# Peripheral.net
KiCad netlist of a schematic drawn in Altium Designer
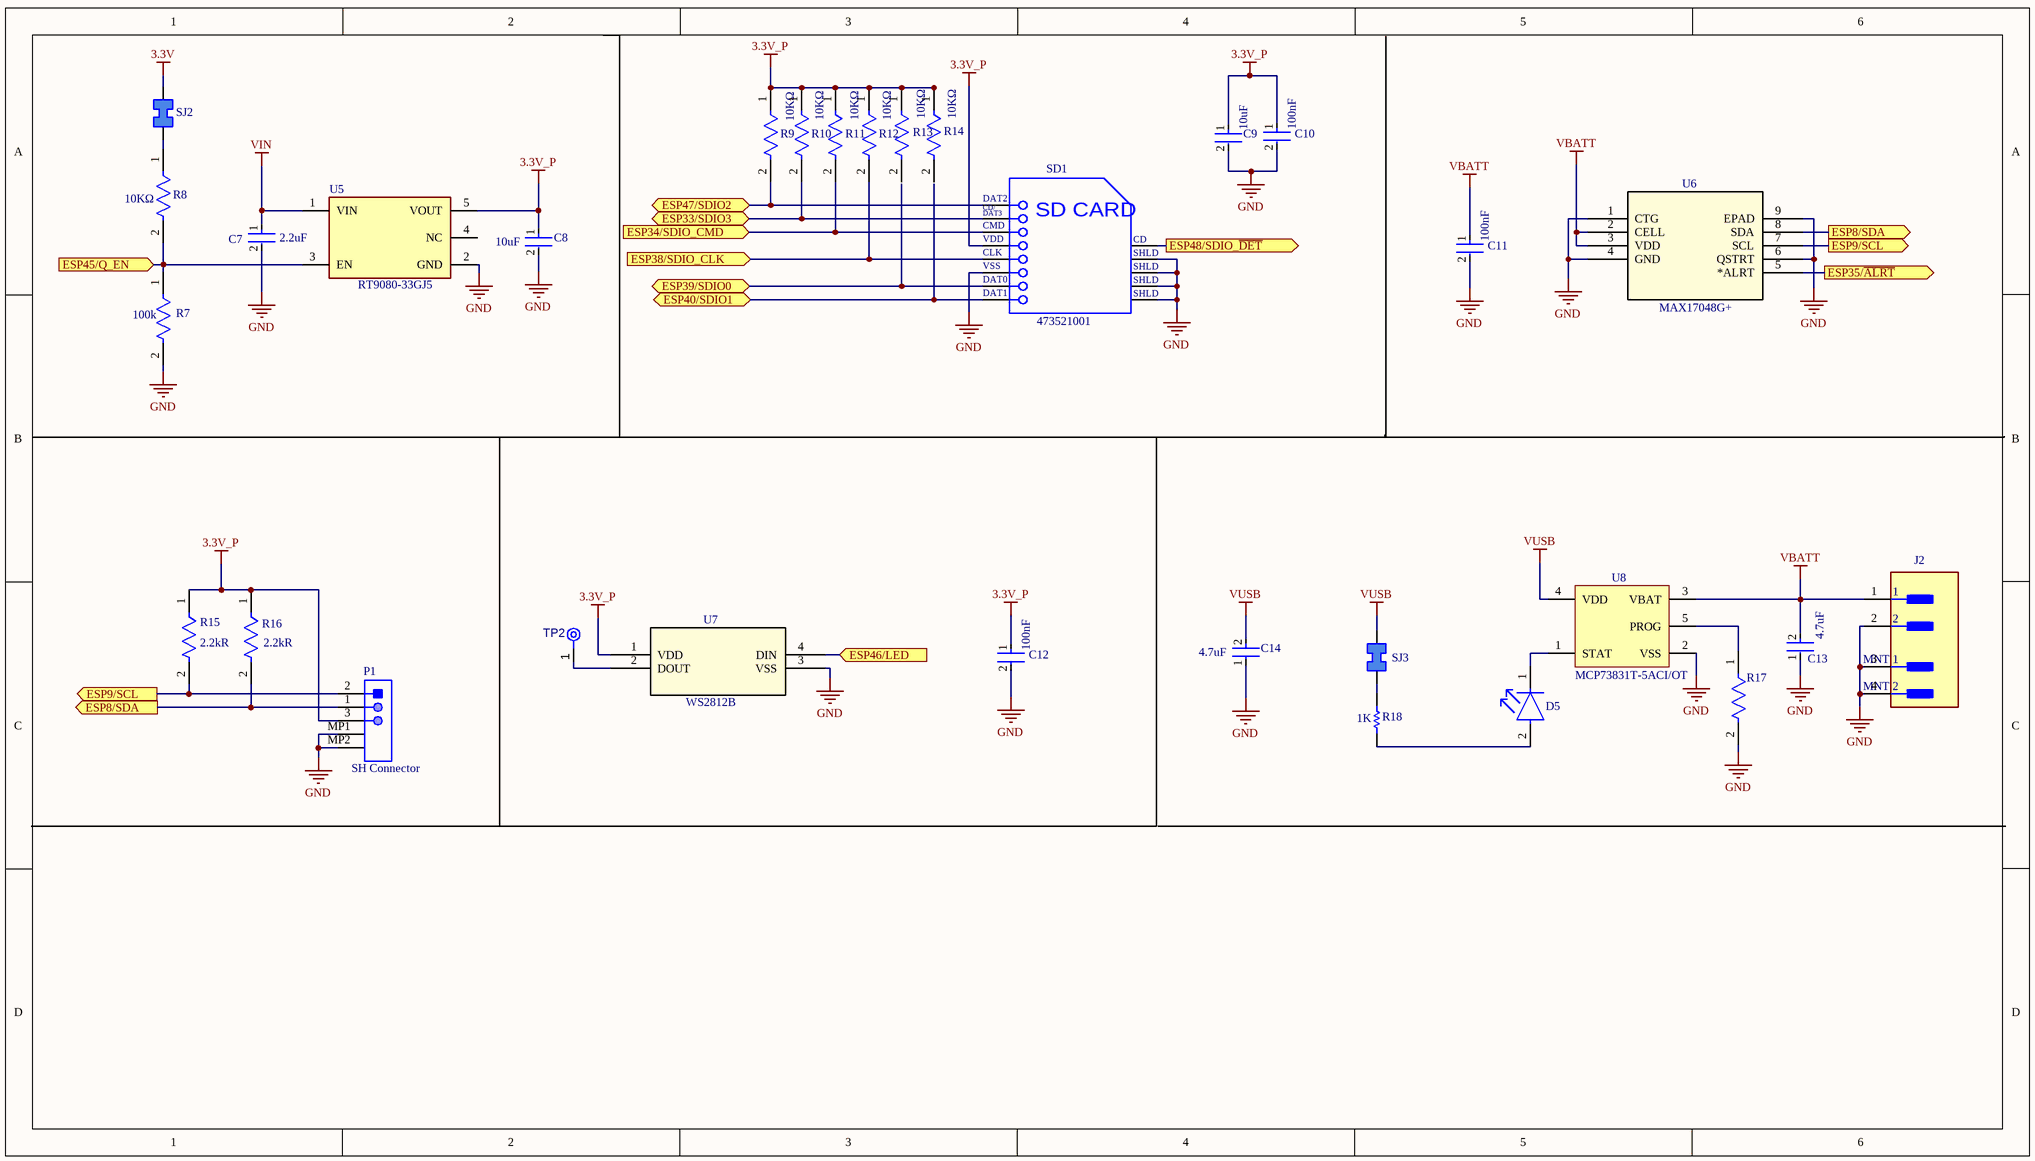
[diagram p0: Peripheral.SchDoc]

(export (version "E")
  (design (tool "Eeschema 10.0.6"))
  (components
    (comp (ref "C7")
      (value "GRM155C81A225KE44D")
      (footprint "FP-GRM155-0_1-IPC_C")
      (description "Chip Multilayer Ceramic Capacitors for General Purpose, 0402, 2.2uF, X6S, 22%, 10%, 10V")
      (fields (field (name "TOLERANCE") "10%") (field (name "CAPACITANCE") "2.2uF"))
      (libsource (lib "Altium Content Vault") (part "11868f565c42a9108669ba33697ecf6"))
    )
    (comp (ref "C8")
      (value "CL21A106MQFNNNE")
      (footprint "FP-CL21-IPC_C")
      (description "CL21 Series 0805 10uF 6.3V ±20% Tolerance X5R Multilayer Ceramic Chip Capacitor")
      (fields (field (name "CAPACITANCE") "10uF") (field (name "TOLERANCE") "20%"))
      (libsource (lib "Altium Content Vault") (part "b4654b650e69147ec39a6b967a45e02"))
    )
    (comp (ref "C9")
      (value "CL21A106MQFNNNE")
      (footprint "FP-CL21-IPC_C")
      (description "CL21 Series 0805 10uF 6.3V ±20% Tolerance X5R Multilayer Ceramic Chip Capacitor")
      (fields (field (name "CAPACITANCE") "10uF") (field (name "TOLERANCE") "20%"))
      (libsource (lib "Altium Content Vault") (part "b4654b650e69147ec39a6b967a45e02"))
    )
    (comp (ref "C10")
      (value "GRM033C70J104KE14D")
      (footprint "FP-GRM033-0_03-IPC_B")
      (description "Chip Multilayer Ceramic Capacitors for General Purpose, 0201, 0.10uF, X7S, 22%, 10%, 6.3V")
      (fields (field (name "CAPACITANCE") "100nF") (field (name "TOLERANCE") "10%"))
      (libsource (lib "Altium Content Vault") (part "b4654b650e69147ec39a6b967a45e02"))
    )
    (comp (ref "C11")
      (value "GRM033C70J104KE14D")
      (footprint "FP-GRM033-0_03-IPC_B")
      (description "Chip Multilayer Ceramic Capacitors for General Purpose, 0201, 0.10uF, X7S, 22%, 10%, 6.3V")
      (fields (field (name "CAPACITANCE") "100nF") (field (name "TOLERANCE") "10%"))
      (libsource (lib "Altium Content Vault") (part "b4654b650e69147ec39a6b967a45e02"))
    )
    (comp (ref "C12")
      (value "GRM033C70J104KE14D")
      (footprint "FP-GRM033-0_03-IPC_B")
      (description "Chip Multilayer Ceramic Capacitors for General Purpose, 0201, 0.10uF, X7S, 22%, 10%, 6.3V")
      (fields (field (name "CAPACITANCE") "100nF") (field (name "TOLERANCE") "10%"))
      (libsource (lib "Altium Content Vault") (part "b4654b650e69147ec39a6b967a45e02"))
    )
    (comp (ref "C13")
      (value "JMK105BC6475MV-F")
      (footprint "FP-0402-L_1_0_0_15-W_0_5-IPC_C")
      (description "None")
      (fields (field (name "CAPACITANCE") "4.7uF") (field (name "TOLERANCE") "20%"))
      (libsource (lib "Altium Content Vault") (part "236180d848d6139a670b325ea6854c9"))
    )
    (comp (ref "C14")
      (value "GRM219R6YA475MA73D")
      (footprint "FP-GRM219-0_15-0_1-IPC_C")
      (description "Chip Multilayer Ceramic Capacitors for General Purpose, 0805, 4.7uF, X5R, 15%, 20%, 35V")
      (fields
        (field (name "CAPACITANCE") "4.7uF")
        (field (name "VOLTAGE") "35V")
        (field (name "TOLERANCE") "20%")
      )
      (libsource (lib "Altium Content Vault") (part "236180d848d6139a670b325ea6854c9"))
    )
    (comp (ref "D5")
      (value "LTST-C191KSKT")
      (footprint "FP-LTST-C191KSKT-MFG")
      (description "LED YELLOW CLEAR SMD")
      (libsource (lib "Altium Content Vault") (part "8706943c75ba83719d021d2fdc84c58"))
    )
    (comp (ref "J2")
      (value "SM02B-SRSS-TB (LF)(SN)")
      (footprint "FP-SM02B-SRSS-TB_LF_SN-MFG")
      (description "CONN HEADER SMD R/A 2POS 1MM")
      (libsource (lib "Altium Content Vault") (part "029478cb6d4f2fad0cd2a245525ee6d"))
    )
    (comp (ref "P1")
      (value "SH Connector")
      (footprint "JST-SM03B-SRSS-TB_V")
      (description "Male Header, Pitch 1 mm, 1 x 3 Position, Height 2.9 mm, -25 to 85 degC, RoHS, Tape and Reel")
      (fields (field (name "MANUFACTURER") "JST"))
      (libsource (lib "Altium Content Vault") (part "CN-1P-2M-R3"))
    )
    (comp (ref "R7")
      (value "CRCW0402100KFKEDC")
      (footprint "FP-CRCW0402-C-e3-MFG")
      (description "RES 100K OHM 1% 1/16W 0402")
      (fields (field (name "TOLERANCE") "1%") (field (name "RESISTANCE") "100k"))
      (libsource (lib "Altium Content Vault") (part "1029c3af85768c4190bb7ad29bc67b5"))
    )
    (comp (ref "R8")
      (value "10KΩ")
      (footprint "FP-RT0201-MFG")
      (description "RES SMD 10K OHM 1% 1/20W 0201")
      (fields
        (field (name "MANUFACTURER PART NUMBER") "RT0201FRE0710KL")
        (field (name "MANUFACTURER") "Yageo")
      )
      (libsource (lib "Altium Content Vault") (part "1029c3af85768c4190bb7ad29bc67b5"))
    )
    (comp (ref "R9")
      (value "10KΩ")
      (footprint "FP-RT0201-MFG")
      (description "RES SMD 10K OHM 1% 1/20W 0201")
      (fields
        (field (name "MANUFACTURER PART NUMBER") "RT0201FRE0710KL")
        (field (name "MANUFACTURER") "Yageo")
      )
      (libsource (lib "Altium Content Vault") (part "1029c3af85768c4190bb7ad29bc67b5"))
    )
    (comp (ref "R10")
      (value "10KΩ")
      (footprint "FP-RT0201-MFG")
      (description "RES SMD 10K OHM 1% 1/20W 0201")
      (fields
        (field (name "MANUFACTURER PART NUMBER") "RT0201FRE0710KL")
        (field (name "MANUFACTURER") "Yageo")
      )
      (libsource (lib "Altium Content Vault") (part "1029c3af85768c4190bb7ad29bc67b5"))
    )
    (comp (ref "R11")
      (value "10KΩ")
      (footprint "FP-RT0201-MFG")
      (description "RES SMD 10K OHM 1% 1/20W 0201")
      (fields
        (field (name "MANUFACTURER PART NUMBER") "RT0201FRE0710KL")
        (field (name "MANUFACTURER") "Yageo")
      )
      (libsource (lib "Altium Content Vault") (part "1029c3af85768c4190bb7ad29bc67b5"))
    )
    (comp (ref "R12")
      (value "10KΩ")
      (footprint "FP-RT0201-MFG")
      (description "RES SMD 10K OHM 1% 1/20W 0201")
      (fields
        (field (name "MANUFACTURER PART NUMBER") "RT0201FRE0710KL")
        (field (name "MANUFACTURER") "Yageo")
      )
      (libsource (lib "Altium Content Vault") (part "1029c3af85768c4190bb7ad29bc67b5"))
    )
    (comp (ref "R13")
      (value "10KΩ")
      (footprint "FP-RT0201-MFG")
      (description "RES SMD 10K OHM 1% 1/20W 0201")
      (fields
        (field (name "MANUFACTURER PART NUMBER") "RT0201FRE0710KL")
        (field (name "MANUFACTURER") "Yageo")
      )
      (libsource (lib "Altium Content Vault") (part "1029c3af85768c4190bb7ad29bc67b5"))
    )
    (comp (ref "R14")
      (value "10KΩ")
      (footprint "FP-RT0201-MFG")
      (description "RES SMD 10K OHM 1% 1/20W 0201")
      (fields
        (field (name "MANUFACTURER PART NUMBER") "RT0201FRE0710KL")
        (field (name "MANUFACTURER") "Yageo")
      )
      (libsource (lib "Altium Content Vault") (part "1029c3af85768c4190bb7ad29bc67b5"))
    )
    (comp (ref "R15")
      (value "CRCW04022K20FKEDC")
      (footprint "FP-CRCW0402-e3-IPC_B")
      (description "RES 2.2K OHM 1% 1/16W 0402")
      (fields (field (name "TOLERANCE") "1%") (field (name "RESISTANCE") "2.2kR"))
      (libsource (lib "Altium Content Vault") (part "1029c3af85768c4190bb7ad29bc67b5"))
    )
    (comp (ref "R16")
      (value "CRCW04022K20FKEDC")
      (footprint "FP-CRCW0402-e3-IPC_B")
      (description "RES 2.2K OHM 1% 1/16W 0402")
      (fields (field (name "TOLERANCE") "1%") (field (name "RESISTANCE") "2.2kR"))
      (libsource (lib "Altium Content Vault") (part "1029c3af85768c4190bb7ad29bc67b5"))
    )
    (comp (ref "R17")
      (value "CR0402AFX-2001GLF")
      (footprint "FP-CR0402A-IPC_A")
      (description "AEC-Q200 Compliant Chip Resistors 0402 2kΩ 0.063W 1% 100ppm/°C")
      (libsource (lib "Altium Content Vault") (part "1029c3af85768c4190bb7ad29bc67b5"))
    )
    (comp (ref "R18")
      (value "1-1622826-8")
      (footprint "RESC1005X40X25ML10T10")
      (fields (field (name "MANUFACTURER") "TE Connectivity / AMP") (field (name "RESISTANCE") "1K"))
      (libsource (lib "Altium Content Vault") (part "RES"))
    )
    (comp (ref "SD1")
      (value "473521001")
      (footprint "MOLX-473521001_V")
      (description "MicroSD(TM), Pitch 1.1 mm, 8 Position, Height 1.88 mm, -20 to 85 degC, RoHS, Tape and Reel")
      (fields (field (name "MANUFACTURER") "Molex"))
      (libsource (lib "Altium Content Vault") (part "CN-SD-8-1SW-4S"))
    )
    (comp (ref "SJ2")
      (value "Solder Jumper")
      (footprint "Solder Jumper-Footprint-1")
      (description "2 pad Solder Jumper")
      (libsource (lib "Shuvendu Das") (part "Solder Jumper"))
    )
    (comp (ref "SJ3")
      (value "Solder Jumper")
      (footprint "Solder Jumper-Footprint-1")
      (description "2 pad Solder Jumper")
      (libsource (lib "Shuvendu Das") (part "Solder Jumper"))
    )
    (comp (ref "TP2")
      (value "TPAD6R")
      (footprint "TP06R")
      (description "0.6mm round")
      (libsource (lib "Shuvendu Das") (part "CMP-001-0001-4"))
    )
    (comp (ref "U5")
      (value "RT9080-33GJ5")
      (footprint "FP-RT9080-33GJ5-IPC_C")
      (description "IC REG LIN 3.3V 600MA TSOT23-5")
      (libsource (lib "Altium Content Vault") (part "f644620f29190e8f0733f9129712cb2"))
    )
    (comp (ref "U6")
      (value "MAX17048G+")
      (footprint "21-0168_T822+3_MXM")
      (description "3ÂµA 1-Cell/2-Cell Fuel Gauge with ModelGauge")
      (fields (field (name "COPYRIGHT") "Copyright (C) 2025 Ultra Librarian. All rights reserved."))
      (libsource (lib "MAX17048G&plus_") (part "MAX17048G+"))
    )
    (comp (ref "U7")
      (value "WS2812B")
      (footprint "WS2812B:WS2812B_WDS")
      (description "No Description Available")
      (fields (field (name "COPYRIGHT") "Copyright (C) 2025 Ultra Librarian. All rights reserved."))
      (libsource (lib "WS2812B") (part "WS2812B"))
    )
    (comp (ref "U8")
      (value "MCP73831T-5ACI/OT")
      (footprint "SOT-23-OT5_N")
      (libsource (lib "Altium Content Vault") (part "PM-BM-MCP73831-SOT5"))
    )
  )
  (nets
    (net (code "1") (name "/ESP8{slash}SDA") (class "Default")
      (node (ref "P1") (pin "1") (pinfunction "1_1") (pintype "passive"))
      (node (ref "R16") (pin "2") (pinfunction "2_2") (pintype "passive"))
      (node (ref "U6") (pin "8") (pinfunction "SDA_8") (pintype "passive"))
    )
    (net (code "2") (name "/ESP9{slash}SCL") (class "Default")
      (node (ref "P1") (pin "2") (pinfunction "2_2") (pintype "passive"))
      (node (ref "R15") (pin "2") (pinfunction "2_2") (pintype "passive"))
      (node (ref "U6") (pin "7") (pinfunction "SCL_7") (pintype "passive"))
    )
    (net (code "3") (name "/ESP33{slash}SDIO3") (class "Default")
      (node (ref "R10") (pin "2") (pinfunction "2_2") (pintype "passive"))
      (node (ref "SD1") (pin "2") (pinfunction "CD/DAT3_2") (pintype "passive"))
    )
    (net (code "4") (name "/ESP34{slash}SDIO_CMD") (class "Default")
      (node (ref "R11") (pin "2") (pinfunction "2_2") (pintype "passive"))
      (node (ref "SD1") (pin "3") (pinfunction "CMD_3") (pintype "passive"))
    )
    (net (code "5") (name "/ESP35{slash}~{ALRT}") (class "Default")
      (node (ref "U6") (pin "5") (pinfunction "*ALRT_5") (pintype "passive"))
    )
    (net (code "6") (name "/ESP38{slash}SDIO_CLK") (class "Default")
      (node (ref "R12") (pin "2") (pinfunction "2_2") (pintype "passive"))
      (node (ref "SD1") (pin "5") (pinfunction "CLK_5") (pintype "passive"))
    )
    (net (code "7") (name "/ESP39{slash}SDIO0") (class "Default")
      (node (ref "SD1") (pin "7") (pinfunction "DAT0_7") (pintype "passive"))
    )
    (net (code "8") (name "/ESP40{slash}SDIO1") (class "Default")
      (node (ref "SD1") (pin "8") (pinfunction "DAT1_8") (pintype "passive"))
    )
    (net (code "9") (name "/ESP45{slash}Q_EN") (class "Default")
      (node (ref "R7") (pin "1") (pinfunction "1_1") (pintype "passive"))
      (node (ref "R8") (pin "2") (pinfunction "2_2") (pintype "passive"))
      (node (ref "U5") (pin "3") (pinfunction "EN_3") (pintype "passive"))
    )
    (net (code "10") (name "/ESP46{slash}LED") (class "Default")
      (node (ref "U7") (pin "4") (pinfunction "DIN_4") (pintype "passive"))
    )
    (net (code "11") (name "/ESP47{slash}SDIO2") (class "Default")
      (node (ref "R9") (pin "2") (pinfunction "2_2") (pintype "passive"))
      (node (ref "SD1") (pin "1") (pinfunction "DAT2_1") (pintype "passive"))
    )
    (net (code "12") (name "/ESP48{slash}SDIO_~{DET}") (class "Default")
      (node (ref "SD1") (pin "9") (pinfunction "CD_9") (pintype "passive"))
    )
    (net (code "13") (name "3.3V") (class "Default")
      (node (ref "SJ2") (pin "1") (pinfunction "1_1") (pintype "passive"))
    )
    (net (code "14") (name "3.3V_P") (class "Default")
      (node (ref "C10") (pin "1") (pinfunction "1_1") (pintype "passive"))
      (node (ref "C12") (pin "1") (pinfunction "1_1") (pintype "passive"))
      (node (ref "C8") (pin "1") (pinfunction "1_1") (pintype "passive"))
      (node (ref "C9") (pin "1") (pinfunction "1_1") (pintype "passive"))
      (node (ref "P1") (pin "3") (pinfunction "3_3") (pintype "passive"))
      (node (ref "R10") (pin "1") (pinfunction "1_1") (pintype "passive"))
      (node (ref "R11") (pin "1") (pinfunction "1_1") (pintype "passive"))
      (node (ref "R12") (pin "1") (pinfunction "1_1") (pintype "passive"))
      (node (ref "R13") (pin "1") (pinfunction "1_1") (pintype "passive"))
      (node (ref "R14") (pin "1") (pinfunction "1_1") (pintype "passive"))
      (node (ref "R15") (pin "1") (pinfunction "1_1") (pintype "passive"))
      (node (ref "R16") (pin "1") (pinfunction "1_1") (pintype "passive"))
      (node (ref "R9") (pin "1") (pinfunction "1_1") (pintype "passive"))
      (node (ref "SD1") (pin "4") (pinfunction "VDD_4") (pintype "passive"))
      (node (ref "U5") (pin "5") (pinfunction "VOUT_5") (pintype "passive"))
      (node (ref "U7") (pin "1") (pinfunction "VDD_1") (pintype "power_in"))
    )
    (net (code "15") (name "GND") (class "Default")
      (node (ref "C10") (pin "2") (pinfunction "2_2") (pintype "passive"))
      (node (ref "C11") (pin "2") (pinfunction "2_2") (pintype "passive"))
      (node (ref "C12") (pin "2") (pinfunction "2_2") (pintype "passive"))
      (node (ref "C13") (pin "1") (pinfunction "1_1") (pintype "passive"))
      (node (ref "C14") (pin "1") (pinfunction "1_1") (pintype "passive"))
      (node (ref "C7") (pin "2") (pinfunction "2_2") (pintype "passive"))
      (node (ref "C8") (pin "2") (pinfunction "2_2") (pintype "passive"))
      (node (ref "C9") (pin "2") (pinfunction "2_2") (pintype "passive"))
      (node (ref "J2") (pin "2") (pinfunction "2_2") (pintype "passive"))
      (node (ref "J2") (pin "3") (pinfunction "MNT_1_3") (pintype "passive"))
      (node (ref "J2") (pin "4") (pinfunction "MNT_2_4") (pintype "passive"))
      (node (ref "P1") (pin "MP1") (pinfunction "MP1_MP1") (pintype "passive"))
      (node (ref "P1") (pin "MP2") (pinfunction "MP2_MP2") (pintype "passive"))
      (node (ref "R17") (pin "2") (pinfunction "2_2") (pintype "passive"))
      (node (ref "R7") (pin "2") (pinfunction "2_2") (pintype "passive"))
      (node (ref "SD1") (pin "10") (pinfunction "SHLD_10") (pintype "passive"))
      (node (ref "SD1") (pin "11") (pinfunction "SHLD_11") (pintype "passive"))
      (node (ref "SD1") (pin "12") (pinfunction "SHLD_12") (pintype "passive"))
      (node (ref "SD1") (pin "13") (pinfunction "SHLD_13") (pintype "passive"))
      (node (ref "SD1") (pin "6") (pinfunction "VSS_6") (pintype "passive"))
      (node (ref "U5") (pin "2") (pinfunction "GND_2") (pintype "power_in"))
      (node (ref "U6") (pin "1") (pinfunction "CTG_1") (pintype "passive"))
      (node (ref "U6") (pin "4") (pinfunction "GND_4") (pintype "power_in"))
      (node (ref "U6") (pin "6") (pinfunction "QSTRT_6") (pintype "passive"))
      (node (ref "U6") (pin "9") (pinfunction "EPAD_9") (pintype "passive"))
      (node (ref "U7") (pin "3") (pinfunction "VSS_3") (pintype "power_in"))
      (node (ref "U8") (pin "2") (pinfunction "VSS_2") (pintype "power_in"))
    )
    (net (code "16") (name "Net-(D5-A)") (class "Default")
      (node (ref "D5") (pin "2") (pinfunction "A_2") (pintype "passive"))
      (node (ref "R18") (pin "2") (pinfunction "2_2") (pintype "passive"))
    )
    (net (code "17") (name "Net-(D5-C)") (class "Default")
      (node (ref "D5") (pin "1") (pinfunction "C_1") (pintype "passive"))
      (node (ref "U8") (pin "1") (pinfunction "STAT_1") (pintype "passive"))
    )
    (net (code "18") (name "Net-(R8-Pad1)") (class "Default")
      (node (ref "R8") (pin "1") (pinfunction "1_1") (pintype "passive"))
      (node (ref "SJ2") (pin "2") (pinfunction "2_2") (pintype "passive"))
    )
    (net (code "19") (name "Net-(R18-Pad1)") (class "Default")
      (node (ref "R18") (pin "1") (pinfunction "1_1") (pintype "passive"))
      (node (ref "SJ3") (pin "2") (pinfunction "2_2") (pintype "passive"))
    )
    (net (code "20") (name "Net-(TP2-TP)") (class "Default")
      (node (ref "TP2") (pin "1") (pinfunction "TP_1") (pintype "passive"))
      (node (ref "U7") (pin "2") (pinfunction "DOUT_2") (pintype "passive"))
    )
    (net (code "21") (name "Net-(U8-PROG)") (class "Default")
      (node (ref "R17") (pin "1") (pinfunction "1_1") (pintype "passive"))
      (node (ref "U8") (pin "5") (pinfunction "PROG_5") (pintype "passive"))
    )
    (net (code "22") (name "VBATT") (class "Default")
      (node (ref "C11") (pin "1") (pinfunction "1_1") (pintype "passive"))
      (node (ref "C13") (pin "2") (pinfunction "2_2") (pintype "passive"))
      (node (ref "J2") (pin "1") (pinfunction "1_1") (pintype "passive"))
      (node (ref "U6") (pin "2") (pinfunction "CELL_2") (pintype "passive"))
      (node (ref "U6") (pin "3") (pinfunction "VDD_3") (pintype "power_in"))
      (node (ref "U8") (pin "3") (pinfunction "VBAT_3") (pintype "power_in"))
    )
    (net (code "23") (name "VIN") (class "Default")
      (node (ref "C7") (pin "1") (pinfunction "1_1") (pintype "passive"))
      (node (ref "U5") (pin "1") (pinfunction "VIN_1") (pintype "power_in"))
    )
    (net (code "24") (name "VUSB") (class "Default")
      (node (ref "C14") (pin "2") (pinfunction "2_2") (pintype "passive"))
      (node (ref "SJ3") (pin "1") (pinfunction "1_1") (pintype "passive"))
      (node (ref "U8") (pin "4") (pinfunction "VDD_4") (pintype "power_in"))
    )
    (net (code "25") (name "unconnected-(R13-Pad2)") (class "Default")
      (node (ref "R13") (pin "2") (pinfunction "2_2") (pintype "passive"))
    )
    (net (code "26") (name "unconnected-(R14-Pad2)") (class "Default")
      (node (ref "R14") (pin "2") (pinfunction "2_2") (pintype "passive"))
    )
    (net (code "27") (name "unconnected-(U5-NC-Pad4)") (class "Default")
      (node (ref "U5") (pin "4") (pinfunction "NC_4") (pintype "passive"))
    )
  )
)
